# MCU.net
KiCad netlist of a schematic drawn in Altium Designer
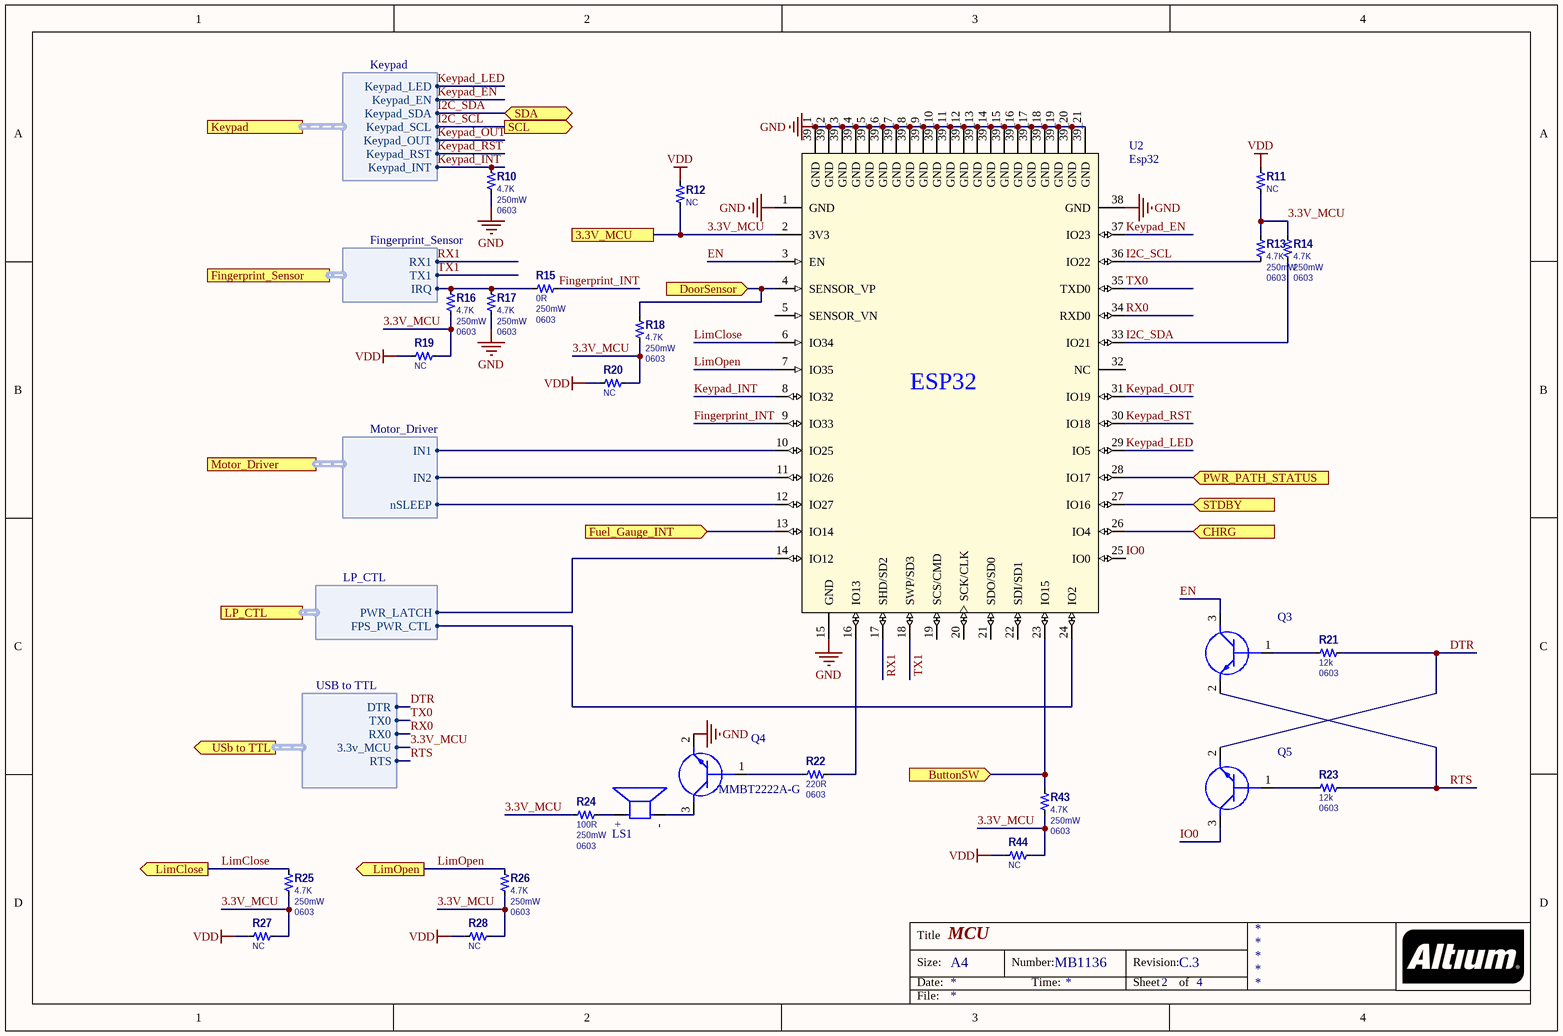
[diagram p0: MCU.SchDoc]

(export (version "E")
  (design (tool "Eeschema 10.0.6"))
  (components
    (comp (ref "LS1")
      (value "AI-1223-TWT-3V-2-R")
      (footprint "XDCR_AI-1223-TWT-3V-2-R")
      (description "AUDIO INDICATOR 82 DB 3 VDC 2300 HZ")
      (fields (field (name "MF") "PUI Audio,"))
      (libsource (lib "Safety_Lock") (part "AI-1223-TWT-3V-2-R"))
    )
    (comp (ref "Q3")
      (value "MMBT2222A-G")
      (footprint "SOT95P240X115-3N")
      (description "Transistor BJT NPN")
      (fields (field (name "MOUSER PART NUMBER") "750-MMBT2222A-G"))
      (libsource (lib "Safety_Lock") (part "MMBT2222A-G_Mirror"))
    )
    (comp (ref "Q4")
      (value "MMBT2222A-G")
      (footprint "SOT95P240X115-3N")
      (description "Transistor BJT NPN")
      (fields (field (name "MOUSER PART NUMBER") "750-MMBT2222A-G"))
      (libsource (lib "Safety_Lock") (part "MMBT2222A-G"))
    )
    (comp (ref "Q5")
      (value "MMBT2222A-G")
      (footprint "SOT95P240X115-3N")
      (description "Transistor BJT NPN")
      (fields (field (name "MOUSER PART NUMBER") "750-MMBT2222A-G"))
      (libsource (lib "Safety_Lock") (part "MMBT2222A-G"))
    )
    (comp (ref "R10")
      (value "4.7K")
      (footprint "0603-R")
      (fields
        (field (name "MANUFACTURER") "Panasonic")
        (field (name "MANUFACTURER PART NUMBER") "ERJ-8GEYJ621V")
        (field (name "TOLERANCE") "5%")
        (field (name "POWER RATING") "250mW")
        (field (name "CASE/PACKAGE") "0603")
      )
      (libsource (lib "Safety_Lock") (part "Res"))
    )
    (comp (ref "R11")
      (value "NC")
      (footprint "0603-R")
      (fields
        (field (name "MANUFACTURER") "Panasonic")
        (field (name "MANUFACTURER PART NUMBER") "ERJ-8GEYJ621V")
        (field (name "TOLERANCE") "5%")
      )
      (libsource (lib "Safety_Lock") (part "Res"))
    )
    (comp (ref "R12")
      (value "NC")
      (footprint "0603-R")
      (fields
        (field (name "MANUFACTURER") "Panasonic")
        (field (name "MANUFACTURER PART NUMBER") "ERJ-8GEYJ621V")
        (field (name "TOLERANCE") "5%")
      )
      (libsource (lib "Safety_Lock") (part "Res"))
    )
    (comp (ref "R13")
      (value "4.7K")
      (footprint "0603-R")
      (fields
        (field (name "MANUFACTURER") "Panasonic")
        (field (name "MANUFACTURER PART NUMBER") "ERJ-8GEYJ621V")
        (field (name "TOLERANCE") "5%")
        (field (name "POWER RATING") "250mW")
        (field (name "CASE/PACKAGE") "0603")
      )
      (libsource (lib "Safety_Lock") (part "Res"))
    )
    (comp (ref "R14")
      (value "4.7K")
      (footprint "0603-R")
      (fields
        (field (name "MANUFACTURER") "Panasonic")
        (field (name "MANUFACTURER PART NUMBER") "ERJ-8GEYJ621V")
        (field (name "TOLERANCE") "5%")
        (field (name "POWER RATING") "250mW")
        (field (name "CASE/PACKAGE") "0603")
      )
      (libsource (lib "Safety_Lock") (part "Res"))
    )
    (comp (ref "R15")
      (value "0R")
      (footprint "0603-R")
      (fields
        (field (name "MANUFACTURER") "Panasonic")
        (field (name "MANUFACTURER PART NUMBER") "ERJ-8GEYJ621V")
        (field (name "TOLERANCE") "5%")
        (field (name "POWER RATING") "250mW")
        (field (name "CASE/PACKAGE") "0603")
      )
      (libsource (lib "Safety_Lock") (part "Res"))
    )
    (comp (ref "R16")
      (value "4.7K")
      (footprint "0603-R")
      (fields
        (field (name "MANUFACTURER") "Panasonic")
        (field (name "MANUFACTURER PART NUMBER") "ERJ-8GEYJ621V")
        (field (name "TOLERANCE") "5%")
        (field (name "POWER RATING") "250mW")
        (field (name "CASE/PACKAGE") "0603")
      )
      (libsource (lib "Safety_Lock") (part "Res"))
    )
    (comp (ref "R17")
      (value "4.7K")
      (footprint "0603-R")
      (fields
        (field (name "MANUFACTURER") "Panasonic")
        (field (name "MANUFACTURER PART NUMBER") "ERJ-8GEYJ621V")
        (field (name "TOLERANCE") "5%")
        (field (name "POWER RATING") "250mW")
        (field (name "CASE/PACKAGE") "0603")
      )
      (libsource (lib "Safety_Lock") (part "Res"))
    )
    (comp (ref "R18")
      (value "4.7K")
      (footprint "0603-R")
      (fields
        (field (name "MANUFACTURER") "Panasonic")
        (field (name "MANUFACTURER PART NUMBER") "ERJ-8GEYJ621V")
        (field (name "TOLERANCE") "5%")
        (field (name "POWER RATING") "250mW")
        (field (name "CASE/PACKAGE") "0603")
      )
      (libsource (lib "Safety_Lock") (part "Res"))
    )
    (comp (ref "R19")
      (value "NC")
      (footprint "0603-R")
      (fields
        (field (name "MANUFACTURER") "Panasonic")
        (field (name "MANUFACTURER PART NUMBER") "ERJ-8GEYJ621V")
        (field (name "TOLERANCE") "5%")
      )
      (libsource (lib "Safety_Lock") (part "Res"))
    )
    (comp (ref "R20")
      (value "NC")
      (footprint "0603-R")
      (fields
        (field (name "MANUFACTURER") "Panasonic")
        (field (name "MANUFACTURER PART NUMBER") "ERJ-8GEYJ621V")
        (field (name "TOLERANCE") "5%")
      )
      (libsource (lib "Safety_Lock") (part "Res"))
    )
    (comp (ref "R21")
      (value "12k")
      (footprint "0603-R")
      (fields
        (field (name "MANUFACTURER") "Panasonic")
        (field (name "MANUFACTURER PART NUMBER") "ERJ-8GEYJ621V")
        (field (name "TOLERANCE") "5%")
        (field (name "CASE/PACKAGE") "0603")
      )
      (libsource (lib "Safety_Lock") (part "Res"))
    )
    (comp (ref "R22")
      (value "220R")
      (footprint "0603-R")
      (fields
        (field (name "MANUFACTURER") "Panasonic")
        (field (name "MANUFACTURER PART NUMBER") "ERJ-8GEYJ621V")
        (field (name "TOLERANCE") "5%")
        (field (name "CASE/PACKAGE") "0603")
      )
      (libsource (lib "Safety_Lock") (part "Res"))
    )
    (comp (ref "R23")
      (value "12k")
      (footprint "0603-R")
      (fields
        (field (name "MANUFACTURER") "Panasonic")
        (field (name "MANUFACTURER PART NUMBER") "ERJ-8GEYJ621V")
        (field (name "TOLERANCE") "5%")
        (field (name "CASE/PACKAGE") "0603")
      )
      (libsource (lib "Safety_Lock") (part "Res"))
    )
    (comp (ref "R24")
      (value "100R")
      (footprint "0603-R")
      (fields
        (field (name "MANUFACTURER") "Panasonic")
        (field (name "MANUFACTURER PART NUMBER") "ERJ-8GEYJ621V")
        (field (name "TOLERANCE") "5%")
        (field (name "POWER RATING") "250mW")
        (field (name "CASE/PACKAGE") "0603")
      )
      (libsource (lib "Safety_Lock") (part "Res"))
    )
    (comp (ref "R25")
      (value "4.7K")
      (footprint "0603-R")
      (fields
        (field (name "MANUFACTURER") "Panasonic")
        (field (name "MANUFACTURER PART NUMBER") "ERJ-8GEYJ621V")
        (field (name "TOLERANCE") "5%")
        (field (name "POWER RATING") "250mW")
        (field (name "CASE/PACKAGE") "0603")
      )
      (libsource (lib "Safety_Lock") (part "Res"))
    )
    (comp (ref "R26")
      (value "4.7K")
      (footprint "0603-R")
      (fields
        (field (name "MANUFACTURER") "Panasonic")
        (field (name "MANUFACTURER PART NUMBER") "ERJ-8GEYJ621V")
        (field (name "TOLERANCE") "5%")
        (field (name "POWER RATING") "250mW")
        (field (name "CASE/PACKAGE") "0603")
      )
      (libsource (lib "Safety_Lock") (part "Res"))
    )
    (comp (ref "R27")
      (value "NC")
      (footprint "0603-R")
      (fields
        (field (name "MANUFACTURER") "Panasonic")
        (field (name "MANUFACTURER PART NUMBER") "ERJ-8GEYJ621V")
        (field (name "TOLERANCE") "5%")
      )
      (libsource (lib "Safety_Lock") (part "Res"))
    )
    (comp (ref "R28")
      (value "NC")
      (footprint "0603-R")
      (fields
        (field (name "MANUFACTURER") "Panasonic")
        (field (name "MANUFACTURER PART NUMBER") "ERJ-8GEYJ621V")
        (field (name "TOLERANCE") "5%")
      )
      (libsource (lib "Safety_Lock") (part "Res"))
    )
    (comp (ref "R43")
      (value "4.7K")
      (footprint "0603-R")
      (fields
        (field (name "MANUFACTURER") "Panasonic")
        (field (name "MANUFACTURER PART NUMBER") "ERJ-8GEYJ621V")
        (field (name "TOLERANCE") "5%")
        (field (name "POWER RATING") "250mW")
        (field (name "CASE/PACKAGE") "0603")
      )
      (libsource (lib "Safety_Lock") (part "Res"))
    )
    (comp (ref "R44")
      (value "NC")
      (footprint "0603-R")
      (fields
        (field (name "MANUFACTURER") "Panasonic")
        (field (name "MANUFACTURER PART NUMBER") "ERJ-8GEYJ621V")
        (field (name "TOLERANCE") "5%")
      )
      (libsource (lib "Safety_Lock") (part "Res"))
    )
    (comp (ref "U2")
      (value "Esp32")
      (footprint "MODULE_ESP32-WROOM-32")
      (description "Bluetooth, WiFi Transceiver Module 2.4GHz ~ 2.5GHz Surface Mount")
      (fields (field (name "MF") "Espressif Systems") (field (name "DIGI-KEY_PART_NUMBER") "1904-1010-1-ND"))
      (libsource (lib "Safety_Lock") (part "ESP32-WROOM-32"))
    )
  )
  (nets
    (net (code "8") (name "/3.3V_MCU") (class "Default")
      (node (ref "R11") (pin "1") (pinfunction "1_1") (pintype "passive"))
      (node (ref "R12") (pin "1") (pinfunction "1_1") (pintype "passive"))
      (node (ref "R13") (pin "1") (pinfunction "1_1") (pintype "passive"))
      (node (ref "R14") (pin "1") (pinfunction "1_1") (pintype "passive"))
      (node (ref "R16") (pin "2") (pinfunction "2_2") (pintype "passive"))
      (node (ref "R18") (pin "2") (pinfunction "2_2") (pintype "passive"))
      (node (ref "R19") (pin "2") (pinfunction "2_2") (pintype "passive"))
      (node (ref "R20") (pin "2") (pinfunction "2_2") (pintype "passive"))
      (node (ref "R24") (pin "1") (pinfunction "1_1") (pintype "passive"))
      (node (ref "R25") (pin "2") (pinfunction "2_2") (pintype "passive"))
      (node (ref "R26") (pin "2") (pinfunction "2_2") (pintype "passive"))
      (node (ref "R27") (pin "2") (pinfunction "2_2") (pintype "passive"))
      (node (ref "R28") (pin "2") (pinfunction "2_2") (pintype "passive"))
      (node (ref "R43") (pin "2") (pinfunction "2_2") (pintype "passive"))
      (node (ref "R44") (pin "2") (pinfunction "2_2") (pintype "passive"))
      (node (ref "U2") (pin "2") (pinfunction "3V3_2") (pintype "power_in"))
    )
    (net (code "9") (name "/ButtonSW") (class "Default")
      (node (ref "R43") (pin "1") (pinfunction "1_1") (pintype "passive"))
      (node (ref "U2") (pin "23") (pinfunction "IO15_23") (pintype "bidirectional"))
    )
    (net (code "10") (name "/CHRG") (class "Default")
      (node (ref "U2") (pin "26") (pinfunction "IO4_26") (pintype "bidirectional"))
    )
    (net (code "11") (name "/DTR") (class "Default")
      (node (ref "Q5") (pin "2") (pinfunction "E_2") (pintype "passive"))
      (node (ref "R21") (pin "1") (pinfunction "1_1") (pintype "passive"))
    )
    (net (code "12") (name "/DoorSensor") (class "Default")
      (node (ref "R18") (pin "1") (pinfunction "1_1") (pintype "passive"))
      (node (ref "U2") (pin "4") (pinfunction "SENSOR_VP_4") (pintype "input"))
    )
    (net (code "13") (name "/EN") (class "Default")
      (node (ref "Q3") (pin "3") (pinfunction "C_3") (pintype "passive"))
      (node (ref "U2") (pin "3") (pinfunction "EN_3") (pintype "input"))
    )
    (net (code "14") (name "/FPS_PWR_CTL") (class "Default")
      (node (ref "U2") (pin "24") (pinfunction "IO2_24") (pintype "bidirectional"))
    )
    (net (code "15") (name "/Fingerprint_INT") (class "Default")
      (node (ref "R15") (pin "2") (pinfunction "2_2") (pintype "passive"))
      (node (ref "U2") (pin "9") (pinfunction "IO33_9") (pintype "bidirectional"))
    )
    (net (code "16") (name "/Fuel_Gauge_INT") (class "Default")
      (node (ref "U2") (pin "13") (pinfunction "IO14_13") (pintype "bidirectional"))
    )
    (net (code "17") (name "/I2C_SCL") (class "Default")
      (node (ref "R13") (pin "2") (pinfunction "2_2") (pintype "passive"))
      (node (ref "U2") (pin "36") (pinfunction "IO22_36") (pintype "bidirectional"))
    )
    (net (code "18") (name "/I2C_SDA") (class "Default")
      (node (ref "R14") (pin "2") (pinfunction "2_2") (pintype "passive"))
      (node (ref "U2") (pin "33") (pinfunction "IO21_33") (pintype "bidirectional"))
    )
    (net (code "19") (name "/IN1") (class "Default")
      (node (ref "U2") (pin "10") (pinfunction "IO25_10") (pintype "bidirectional"))
    )
    (net (code "20") (name "/IN2") (class "Default")
      (node (ref "U2") (pin "11") (pinfunction "IO26_11") (pintype "bidirectional"))
    )
    (net (code "21") (name "/IO0") (class "Default")
      (node (ref "Q5") (pin "3") (pinfunction "C_3") (pintype "passive"))
      (node (ref "U2") (pin "25") (pinfunction "IO0_25") (pintype "bidirectional"))
    )
    (net (code "22") (name "/IRQ") (class "Default")
      (node (ref "R15") (pin "1") (pinfunction "1_1") (pintype "passive"))
      (node (ref "R16") (pin "1") (pinfunction "1_1") (pintype "passive"))
      (node (ref "R17") (pin "1") (pinfunction "1_1") (pintype "passive"))
    )
    (net (code "23") (name "/Keypad_EN") (class "Default")
      (node (ref "U2") (pin "37") (pinfunction "IO23_37") (pintype "bidirectional"))
    )
    (net (code "24") (name "/Keypad_INT") (class "Default")
      (node (ref "R10") (pin "1") (pinfunction "1_1") (pintype "passive"))
      (node (ref "U2") (pin "8") (pinfunction "IO32_8") (pintype "bidirectional"))
    )
    (net (code "25") (name "/Keypad_LED") (class "Default")
      (node (ref "U2") (pin "29") (pinfunction "IO5_29") (pintype "bidirectional"))
    )
    (net (code "26") (name "/Keypad_OUT") (class "Default")
      (node (ref "U2") (pin "31") (pinfunction "IO19_31") (pintype "bidirectional"))
    )
    (net (code "27") (name "/Keypad_RST") (class "Default")
      (node (ref "U2") (pin "30") (pinfunction "IO18_30") (pintype "bidirectional"))
    )
    (net (code "28") (name "/LimClose") (class "Default")
      (node (ref "R25") (pin "1") (pinfunction "1_1") (pintype "passive"))
      (node (ref "U2") (pin "6") (pinfunction "IO34_6") (pintype "input"))
    )
    (net (code "29") (name "/LimOpen") (class "Default")
      (node (ref "R26") (pin "1") (pinfunction "1_1") (pintype "passive"))
      (node (ref "U2") (pin "7") (pinfunction "IO35_7") (pintype "input"))
    )
    (net (code "30") (name "/PWR_LATCH") (class "Default")
      (node (ref "U2") (pin "14") (pinfunction "IO12_14") (pintype "bidirectional"))
    )
    (net (code "31") (name "/PWR_PATH_STATUS") (class "Default")
      (node (ref "U2") (pin "28") (pinfunction "IO17_28") (pintype "bidirectional"))
    )
    (net (code "32") (name "/RTS") (class "Default")
      (node (ref "Q3") (pin "2") (pinfunction "E_2") (pintype "passive"))
      (node (ref "R23") (pin "1") (pinfunction "1_1") (pintype "passive"))
    )
    (net (code "33") (name "/RX0") (class "Default")
      (node (ref "U2") (pin "34") (pinfunction "RXD0_34") (pintype "bidirectional"))
    )
    (net (code "34") (name "/RX1") (class "Default")
      (node (ref "U2") (pin "17") (pinfunction "SHD/SD2_17") (pintype "bidirectional"))
    )
    (net (code "35") (name "/STDBY") (class "Default")
      (node (ref "U2") (pin "27") (pinfunction "IO16_27") (pintype "bidirectional"))
    )
    (net (code "36") (name "/TX0") (class "Default")
      (node (ref "U2") (pin "35") (pinfunction "TXD0_35") (pintype "bidirectional"))
    )
    (net (code "37") (name "/TX1") (class "Default")
      (node (ref "U2") (pin "18") (pinfunction "SWP/SD3_18") (pintype "bidirectional"))
    )
    (net (code "38") (name "/nSLEEP") (class "Default")
      (node (ref "U2") (pin "12") (pinfunction "IO27_12") (pintype "bidirectional"))
    )
    (net (code "44") (name "GND") (class "Default")
      (node (ref "Q4") (pin "2") (pinfunction "E_2") (pintype "passive"))
      (node (ref "R10") (pin "2") (pinfunction "2_2") (pintype "passive"))
      (node (ref "R17") (pin "2") (pinfunction "2_2") (pintype "passive"))
      (node (ref "U2") (pin "1") (pinfunction "GND_1") (pintype "power_in"))
      (node (ref "U2") (pin "15") (pinfunction "GND_15") (pintype "power_in"))
      (node (ref "U2") (pin "38") (pinfunction "GND_38") (pintype "power_in"))
      (node (ref "U2") (pin "39_1") (pinfunction "GND_39_1") (pintype "power_in"))
      (node (ref "U2") (pin "39_10") (pinfunction "GND_39_10") (pintype "power_in"))
      (node (ref "U2") (pin "39_11") (pinfunction "GND_39_11") (pintype "power_in"))
      (node (ref "U2") (pin "39_12") (pinfunction "GND_39_12") (pintype "power_in"))
      (node (ref "U2") (pin "39_13") (pinfunction "GND_39_13") (pintype "power_in"))
      (node (ref "U2") (pin "39_14") (pinfunction "GND_39_14") (pintype "power_in"))
      (node (ref "U2") (pin "39_15") (pinfunction "GND_39_15") (pintype "power_in"))
      (node (ref "U2") (pin "39_16") (pinfunction "GND_39_16") (pintype "power_in"))
      (node (ref "U2") (pin "39_17") (pinfunction "GND_39_17") (pintype "power_in"))
      (node (ref "U2") (pin "39_18") (pinfunction "GND_39_18") (pintype "power_in"))
      (node (ref "U2") (pin "39_19") (pinfunction "GND_39_19") (pintype "power_in"))
      (node (ref "U2") (pin "39_2") (pinfunction "GND_39_2") (pintype "power_in"))
      (node (ref "U2") (pin "39_20") (pinfunction "GND_39_20") (pintype "power_in"))
      (node (ref "U2") (pin "39_21") (pinfunction "GND_39_21") (pintype "power_in"))
      (node (ref "U2") (pin "39_3") (pinfunction "GND_39_3") (pintype "power_in"))
      (node (ref "U2") (pin "39_4") (pinfunction "GND_39_4") (pintype "power_in"))
      (node (ref "U2") (pin "39_5") (pinfunction "GND_39_5") (pintype "power_in"))
      (node (ref "U2") (pin "39_6") (pinfunction "GND_39_6") (pintype "power_in"))
      (node (ref "U2") (pin "39_7") (pinfunction "GND_39_7") (pintype "power_in"))
      (node (ref "U2") (pin "39_8") (pinfunction "GND_39_8") (pintype "power_in"))
      (node (ref "U2") (pin "39_9") (pinfunction "GND_39_9") (pintype "power_in"))
    )
    (net (code "45") (name "Net-(LS1-PadP)") (class "Default")
      (node (ref "LS1") (pin "P") (pinfunction "P_P") (pintype "passive"))
      (node (ref "R24") (pin "2") (pinfunction "2_2") (pintype "passive"))
    )
    (net (code "46") (name "Net-(Q3-B)") (class "Default")
      (node (ref "Q3") (pin "1") (pinfunction "B_1") (pintype "passive"))
      (node (ref "R21") (pin "2") (pinfunction "2_2") (pintype "passive"))
    )
    (net (code "47") (name "Net-(Q4-B)") (class "Default")
      (node (ref "Q4") (pin "1") (pinfunction "B_1") (pintype "passive"))
      (node (ref "R22") (pin "2") (pinfunction "2_2") (pintype "passive"))
    )
    (net (code "48") (name "Net-(Q4-C)") (class "Default")
      (node (ref "LS1") (pin "N") (pinfunction "N_N") (pintype "passive"))
      (node (ref "Q4") (pin "3") (pinfunction "C_3") (pintype "passive"))
    )
    (net (code "49") (name "Net-(Q5-B)") (class "Default")
      (node (ref "Q5") (pin "1") (pinfunction "B_1") (pintype "passive"))
      (node (ref "R23") (pin "2") (pinfunction "2_2") (pintype "passive"))
    )
    (net (code "50") (name "Net-(U2-IO13)") (class "Default")
      (node (ref "R22") (pin "1") (pinfunction "1_1") (pintype "passive"))
      (node (ref "U2") (pin "16") (pinfunction "IO13_16") (pintype "bidirectional"))
    )
    (net (code "51") (name "VDD") (class "Default")
      (node (ref "R11") (pin "2") (pinfunction "2_2") (pintype "passive"))
      (node (ref "R12") (pin "2") (pinfunction "2_2") (pintype "passive"))
      (node (ref "R19") (pin "1") (pinfunction "1_1") (pintype "passive"))
      (node (ref "R20") (pin "1") (pinfunction "1_1") (pintype "passive"))
      (node (ref "R27") (pin "1") (pinfunction "1_1") (pintype "passive"))
      (node (ref "R28") (pin "1") (pinfunction "1_1") (pintype "passive"))
      (node (ref "R44") (pin "1") (pinfunction "1_1") (pintype "passive"))
    )
    (net (code "52") (name "unconnected-(U2-NC-Pad32)") (class "Default")
      (node (ref "U2") (pin "32") (pinfunction "NC_32") (pintype "passive"))
    )
    (net (code "53") (name "unconnected-(U2-SCK{slash}CLK-Pad20)") (class "Default")
      (node (ref "U2") (pin "20") (pinfunction "SCK/CLK_20") (pintype "bidirectional"))
    )
    (net (code "54") (name "unconnected-(U2-SCS{slash}CMD-Pad19)") (class "Default")
      (node (ref "U2") (pin "19") (pinfunction "SCS/CMD_19") (pintype "bidirectional"))
    )
    (net (code "55") (name "unconnected-(U2-SDI{slash}SD1-Pad22)") (class "Default")
      (node (ref "U2") (pin "22") (pinfunction "SDI/SD1_22") (pintype "bidirectional"))
    )
    (net (code "56") (name "unconnected-(U2-SDO{slash}SD0-Pad21)") (class "Default")
      (node (ref "U2") (pin "21") (pinfunction "SDO/SD0_21") (pintype "bidirectional"))
    )
    (net (code "57") (name "unconnected-(U2-SENSOR_VN-Pad5)") (class "Default")
      (node (ref "U2") (pin "5") (pinfunction "SENSOR_VN_5") (pintype "input"))
    )
  )
)
